# AS5147P.net
KiCad netlist of a schematic drawn in EasyEDA Pro
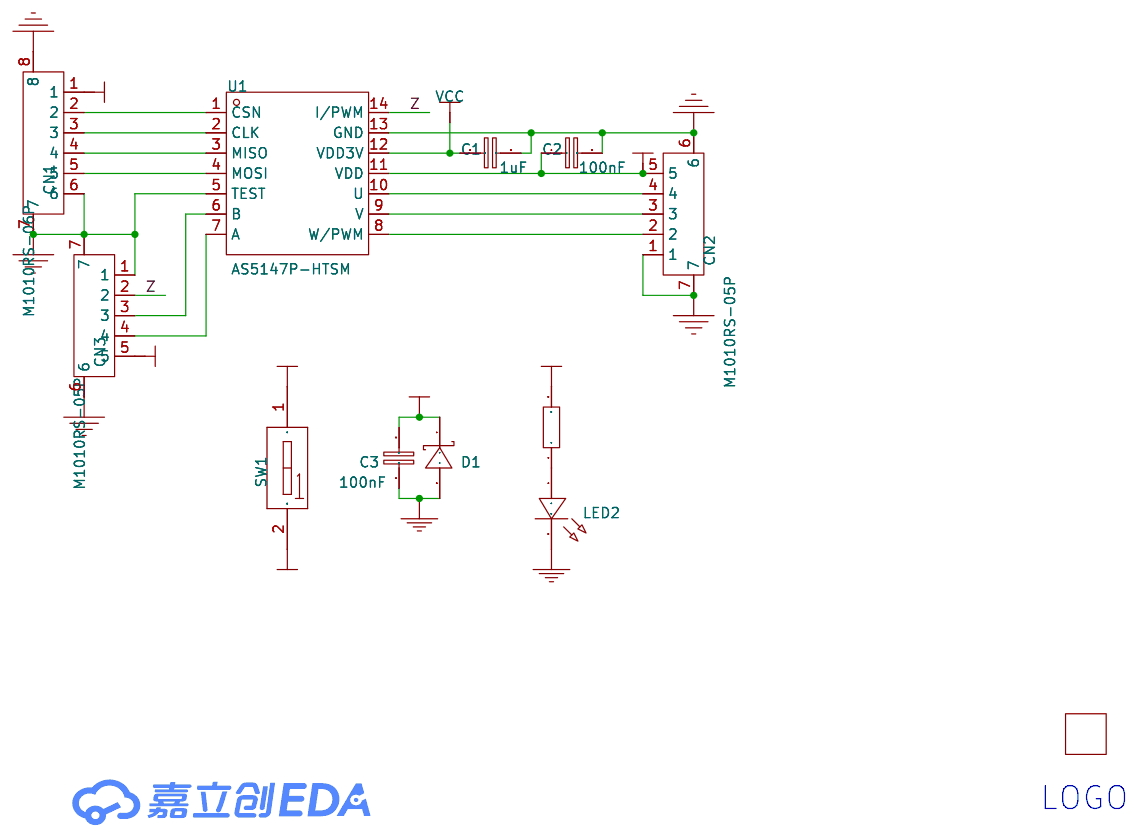
[diagram p0: schematic sheet]

(export (version "E")
  (design (tool "Eeschema 10.0.6"))
  (components
    (comp (ref "C1")
      (value "1uF")
      (fields
        (field (name "Manufacturer Part") "CL10A105KB8NNNC")
        (field (name "Manufacturer") "SAMSUNG(三星)")
      )
      (libsource (lib "easyedapro") (part "C0603"))
    )
    (comp (ref "C2")
      (value "100nF")
      (fields
        (field (name "Manufacturer Part") "CC0603KRX7R9BB104")
        (field (name "Manufacturer") "YAGEO(国巨)")
      )
      (libsource (lib "easyedapro") (part "C0603"))
    )
    (comp (ref "C3")
      (value "100nF")
      (fields
        (field (name "Manufacturer Part") "CC0603KRX7R9BB104")
        (field (name "Manufacturer") "YAGEO(国巨)")
      )
      (libsource (lib "easyedapro") (part "C0603"))
    )
    (comp (ref "CN1")
      (value "M1010RS-06P")
      (footprint "easyedapro:CONN-SMD_M1010RS-06P")
      (description "插针结构:1x6P;间距:1mm;安装方式:卧贴;参考系列:-;总PIN数:6P;排数:1;每排PIN数:6;行距:-;额定电流:1A;工作温度范围:-25°C~+85°C;")
      (fields (field (name "Manufacturer") "XFCN(兴飞)"))
      (libsource (lib "easyedapro") (part "M1010RS-06P"))
    )
    (comp (ref "CN2")
      (value "M1010RS-05P")
      (footprint "easyedapro:CONN-SMD_M1010RS-05P")
      (description "插针结构:1x5P;间距:1mm;安装方式:卧贴;参考系列:-;总PIN数:5P;排数:1;每排PIN数:5;行距:-;额定电流:1A;工作温度范围:-25°C~+85°C;")
      (fields (field (name "Manufacturer") "XFCN(兴飞)"))
      (libsource (lib "easyedapro") (part "M1010RS-05P"))
    )
    (comp (ref "CN3")
      (value "M1010RS-05P")
      (footprint "easyedapro:CONN-SMD_M1010RS-05P")
      (description "插针结构:1x5P;间距:1mm;安装方式:卧贴;参考系列:-;总PIN数:5P;排数:1;每排PIN数:5;行距:-;额定电流:1A;工作温度范围:-25°C~+85°C;")
      (fields (field (name "Manufacturer") "XFCN(兴飞)"))
      (libsource (lib "easyedapro") (part "M1010RS-05P"))
    )
    (comp (ref "D1") (value "SMFJ5.0A") (libsource (lib "easyedapro") (part "SMFJ5.0A")))
    (comp (ref "H1")
      (value "MoonGrt")
      (footprint "easyedapro:MoonGrt")
      (libsource (lib "easyedapro") (part "MoonGrt"))
    )
    (comp (ref "LED2")
      (value "~")
      (footprint "easyedapro:LED0603")
      (libsource (lib "easyedapro") (part "LED0603B"))
    )
    (comp (ref "R2")
      (value "1kΩ")
      (footprint "easyedapro:R0603")
      (libsource (lib "easyedapro") (part "R0603"))
    )
    (comp (ref "SW1") (value "DSHP01TSGET") (libsource (lib "easyedapro") (part "DSHP01TSGET")))
    (comp (ref "U1")
      (value "AS5147P-HTSM")
      (footprint "easyedapro:TSSOP-14_L5.0-W4.4-P0.65-LS6.5-BL")
      (fields (field (name "Manufacturer") "AMS"))
      (libsource (lib "easyedapro") (part "AS5147P-HTSM"))
    )
  )
  (nets
    (net (code "1") (name "/Z") (class "Default")
      (node (ref "CN3") (pin "2") (pinfunction "2_2") (pintype "unspecified"))
      (node (ref "U1") (pin "14") (pinfunction "I/PWM_14") (pintype "unspecified"))
    )
    (net (code "2") (name "5V") (class "Default")
      (node (ref "C2") (pin "1") (pinfunction "1_1") (pintype "unspecified"))
      (node (ref "CN1") (pin "1") (pinfunction "1_1") (pintype "unspecified"))
      (node (ref "CN2") (pin "5") (pinfunction "5_5") (pintype "unspecified"))
      (node (ref "CN3") (pin "5") (pinfunction "5_5") (pintype "unspecified"))
      (node (ref "SW1") (pin "2") (pinfunction "B1_2") (pintype "input"))
      (node (ref "U1") (pin "11") (pinfunction "VDD_11") (pintype "unspecified"))
    )
    (net (code "3") (name "GND") (class "Default")
      (node (ref "C1") (pin "2") (pinfunction "2_2") (pintype "unspecified"))
      (node (ref "C2") (pin "2") (pinfunction "2_2") (pintype "unspecified"))
      (node (ref "C3") (pin "1") (pinfunction "1_1") (pintype "unspecified"))
      (node (ref "CN1") (pin "6") (pinfunction "6_6") (pintype "unspecified"))
      (node (ref "CN1") (pin "7") (pinfunction "7_7") (pintype "unspecified"))
      (node (ref "CN1") (pin "8") (pinfunction "8_8") (pintype "unspecified"))
      (node (ref "CN2") (pin "1") (pinfunction "1_1") (pintype "unspecified"))
      (node (ref "CN2") (pin "6") (pinfunction "6_6") (pintype "unspecified"))
      (node (ref "CN2") (pin "7") (pinfunction "7_7") (pintype "unspecified"))
      (node (ref "CN3") (pin "1") (pinfunction "1_1") (pintype "unspecified"))
      (node (ref "CN3") (pin "6") (pinfunction "6_6") (pintype "unspecified"))
      (node (ref "CN3") (pin "7") (pinfunction "7_7") (pintype "unspecified"))
      (node (ref "D1") (pin "2") (pinfunction "A_2") (pintype "unspecified"))
      (node (ref "LED2") (pin "2") (pinfunction "2_2") (pintype "unspecified"))
      (node (ref "U1") (pin "13") (pinfunction "GND_13") (pintype "unspecified"))
      (node (ref "U1") (pin "5") (pinfunction "TEST_5") (pintype "unspecified"))
    )
    (net (code "4") (name "Net-(LED2-Pad1)") (class "Default")
      (node (ref "LED2") (pin "1") (pinfunction "1_1") (pintype "unspecified"))
      (node (ref "R2") (pin "1") (pinfunction "1_1") (pintype "unspecified"))
    )
    (net (code "5") (name "Net-(U1-A)") (class "Default")
      (node (ref "CN3") (pin "4") (pinfunction "4_4") (pintype "unspecified"))
      (node (ref "U1") (pin "7") (pinfunction "A_7") (pintype "unspecified"))
    )
    (net (code "6") (name "Net-(U1-B)") (class "Default")
      (node (ref "CN3") (pin "3") (pinfunction "3_3") (pintype "unspecified"))
      (node (ref "U1") (pin "6") (pinfunction "B_6") (pintype "unspecified"))
    )
    (net (code "7") (name "Net-(U1-CLK)") (class "Default")
      (node (ref "CN1") (pin "3") (pinfunction "3_3") (pintype "unspecified"))
      (node (ref "U1") (pin "2") (pinfunction "CLK_2") (pintype "unspecified"))
    )
    (net (code "8") (name "Net-(U1-CSN)") (class "Default")
      (node (ref "CN1") (pin "2") (pinfunction "2_2") (pintype "unspecified"))
      (node (ref "U1") (pin "1") (pinfunction "CSN_1") (pintype "unspecified"))
    )
    (net (code "9") (name "Net-(U1-MISO)") (class "Default")
      (node (ref "CN1") (pin "4") (pinfunction "4_4") (pintype "unspecified"))
      (node (ref "U1") (pin "3") (pinfunction "MISO_3") (pintype "unspecified"))
    )
    (net (code "10") (name "Net-(U1-MOSI)") (class "Default")
      (node (ref "CN1") (pin "5") (pinfunction "5_5") (pintype "unspecified"))
      (node (ref "U1") (pin "4") (pinfunction "MOSI_4") (pintype "unspecified"))
    )
    (net (code "11") (name "Net-(U1-U)") (class "Default")
      (node (ref "CN2") (pin "4") (pinfunction "4_4") (pintype "unspecified"))
      (node (ref "U1") (pin "10") (pinfunction "U_10") (pintype "unspecified"))
    )
    (net (code "12") (name "Net-(U1-V)") (class "Default")
      (node (ref "CN2") (pin "3") (pinfunction "3_3") (pintype "unspecified"))
      (node (ref "U1") (pin "9") (pinfunction "V_9") (pintype "unspecified"))
    )
    (net (code "13") (name "Net-(U1-W{slash}PWM)") (class "Default")
      (node (ref "CN2") (pin "2") (pinfunction "2_2") (pintype "unspecified"))
      (node (ref "U1") (pin "8") (pinfunction "W/PWM_8") (pintype "unspecified"))
    )
    (net (code "14") (name "VCC") (class "Default")
      (node (ref "C1") (pin "1") (pinfunction "1_1") (pintype "unspecified"))
      (node (ref "C3") (pin "2") (pinfunction "2_2") (pintype "unspecified"))
      (node (ref "D1") (pin "1") (pinfunction "K_1") (pintype "unspecified"))
      (node (ref "R2") (pin "2") (pinfunction "2_2") (pintype "unspecified"))
      (node (ref "SW1") (pin "1") (pinfunction "A1_1") (pintype "input"))
      (node (ref "U1") (pin "12") (pinfunction "VDD3V_12") (pintype "unspecified"))
    )
  )
)
